# SmartCart-B1-Modules.net
KiCad netlist of a schematic drawn in EasyEDA
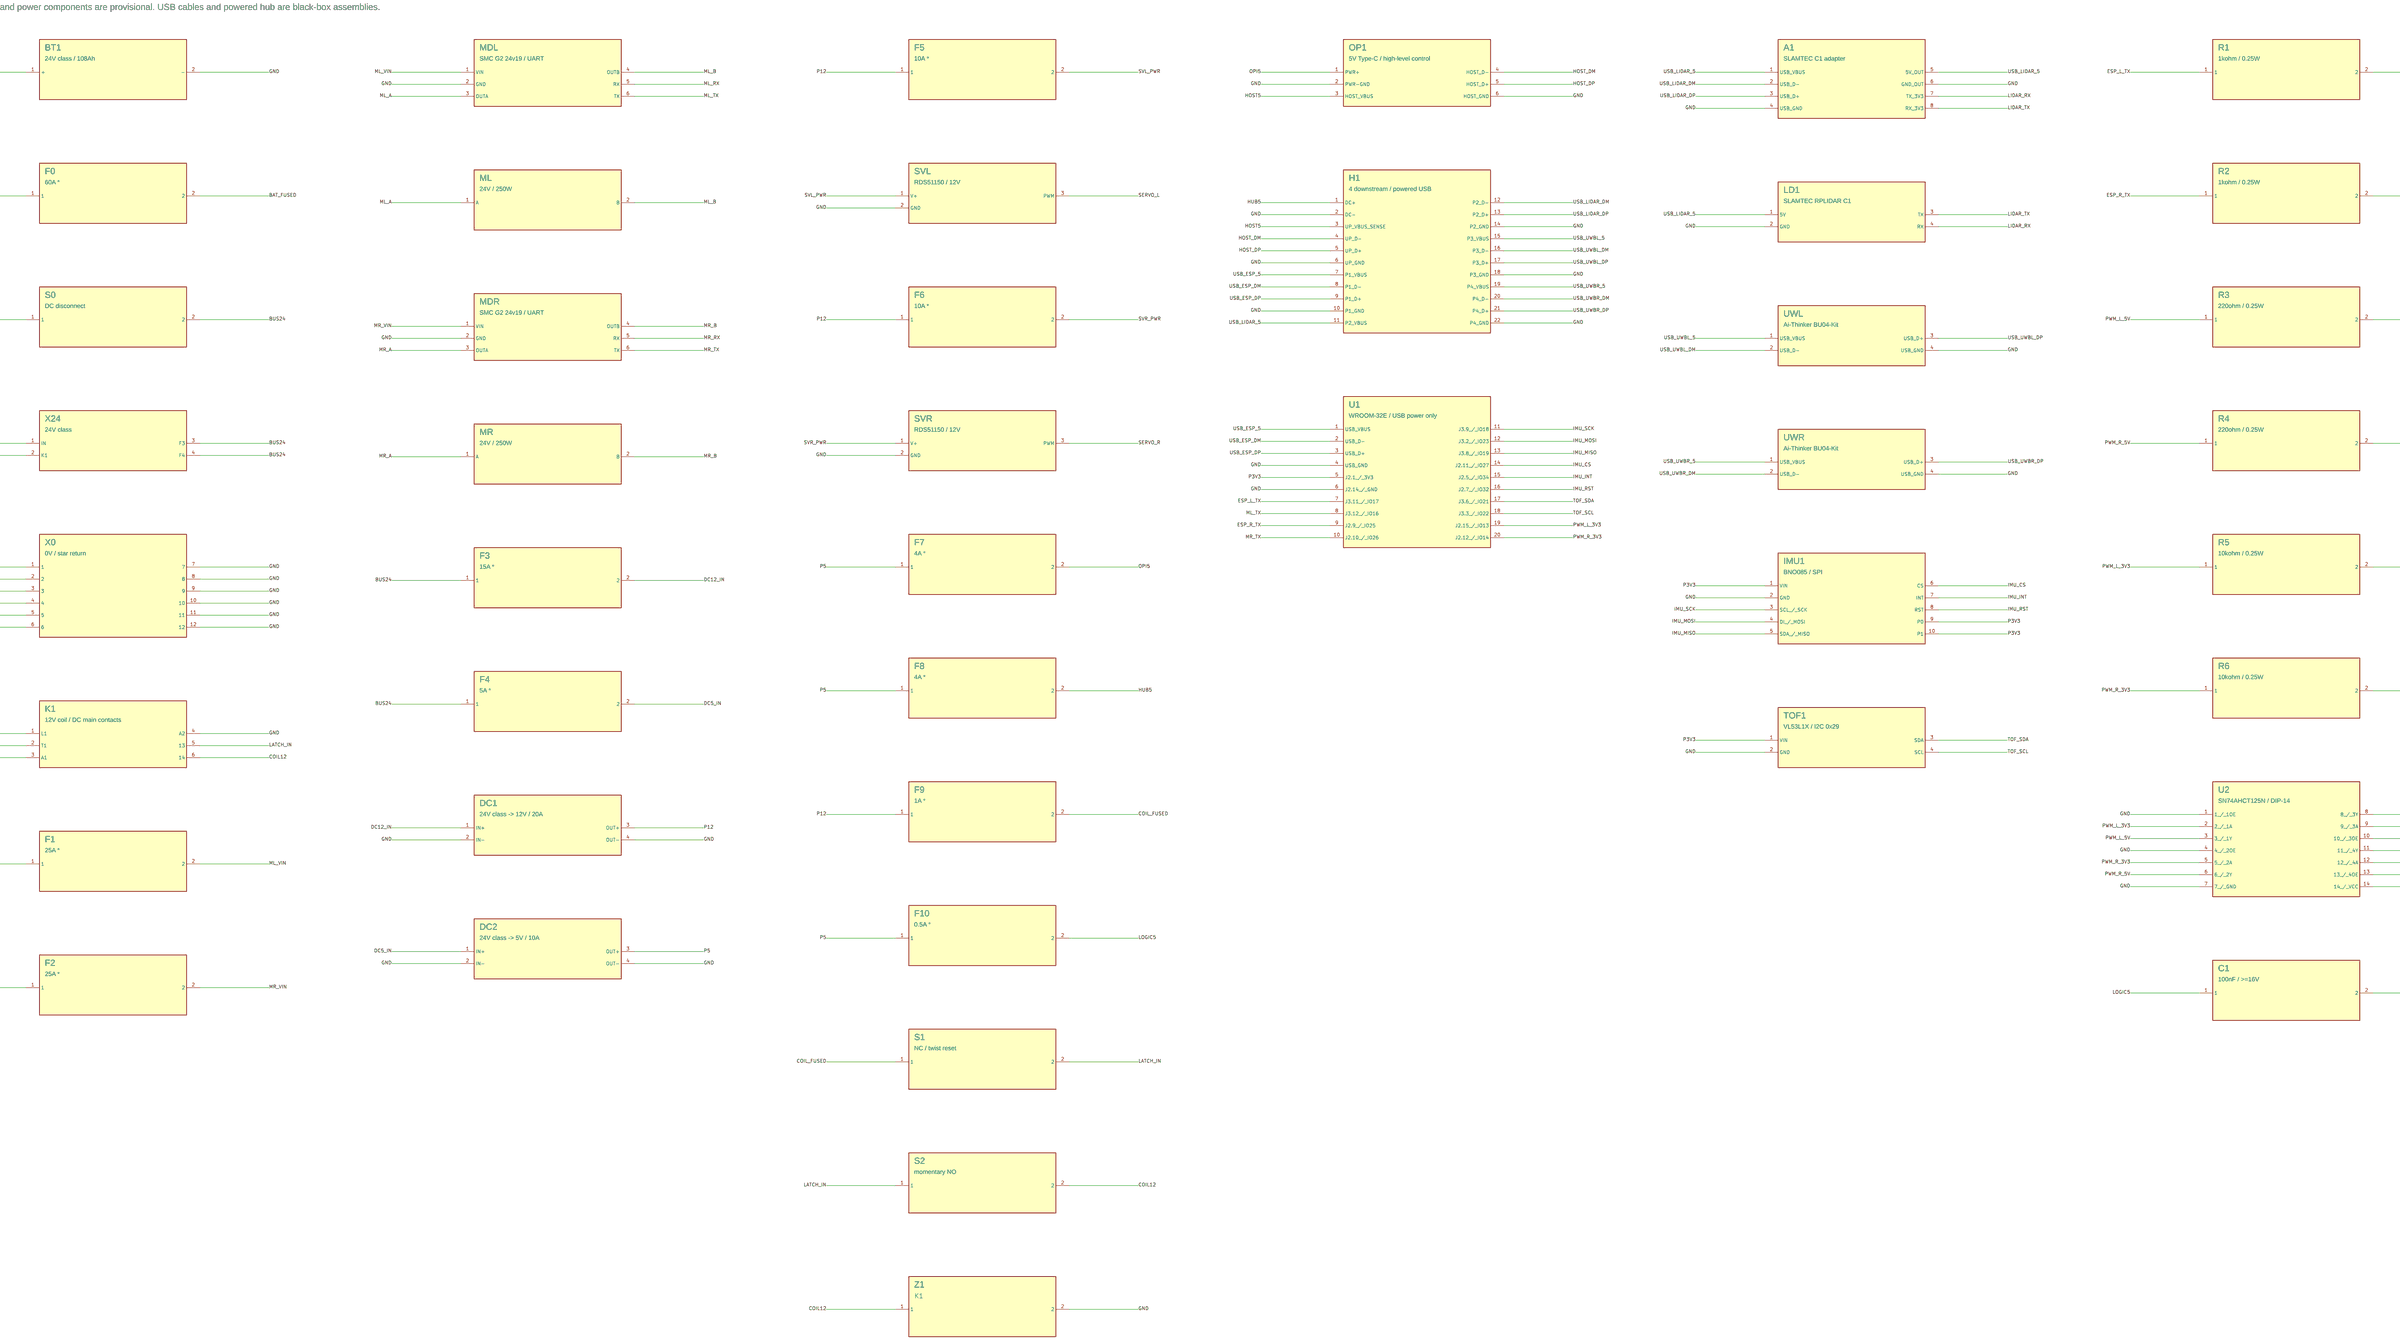
[diagram p0: schematic sheet]

(export (version "E")
  (design (tool "Eeschema 10.0.6"))
  (components
    (comp (ref "A1") (value "SLAMTEC C1 adapter") (libsource (lib "") (part "A1")))
    (comp (ref "BT1") (value "24V class / 108Ah") (libsource (lib "") (part "BT1")))
    (comp (ref "C1") (value "100nF / >=16V") (libsource (lib "") (part "C1")))
    (comp (ref "DC1") (value "24V class -> 12V / 20A") (libsource (lib "") (part "DC1")))
    (comp (ref "DC2") (value "24V class -> 5V / 10A") (libsource (lib "") (part "DC2")))
    (comp (ref "F0") (value "60A *") (libsource (lib "") (part "F0")))
    (comp (ref "F1") (value "25A *") (libsource (lib "") (part "F1")))
    (comp (ref "F2") (value "25A *") (libsource (lib "") (part "F2")))
    (comp (ref "F3") (value "15A *") (libsource (lib "") (part "F3")))
    (comp (ref "F4") (value "5A *") (libsource (lib "") (part "F4")))
    (comp (ref "F5") (value "10A *") (libsource (lib "") (part "F5")))
    (comp (ref "F6") (value "10A *") (libsource (lib "") (part "F6")))
    (comp (ref "F7") (value "4A *") (libsource (lib "") (part "F7")))
    (comp (ref "F8") (value "4A *") (libsource (lib "") (part "F8")))
    (comp (ref "F9") (value "1A *") (libsource (lib "") (part "F9")))
    (comp (ref "F10") (value "0.5A *") (libsource (lib "") (part "F10")))
    (comp (ref "H1") (value "4 downstream / powered USB") (libsource (lib "") (part "H1")))
    (comp (ref "IMU1") (value "BNO085 / SPI") (libsource (lib "") (part "IMU1")))
    (comp (ref "K1") (value "12V coil / DC main contacts") (libsource (lib "") (part "K1")))
    (comp (ref "LD1") (value "SLAMTEC RPLIDAR C1") (libsource (lib "") (part "LD1")))
    (comp (ref "MDL") (value "SMC G2 24v19 / UART") (libsource (lib "") (part "MDL")))
    (comp (ref "MDR") (value "SMC G2 24v19 / UART") (libsource (lib "") (part "MDR")))
    (comp (ref "ML") (value "24V / 250W") (libsource (lib "") (part "ML")))
    (comp (ref "MR") (value "24V / 250W") (libsource (lib "") (part "MR")))
    (comp (ref "OP1") (value "5V Type-C / high-level control") (libsource (lib "") (part "OP1")))
    (comp (ref "R1") (value "1kohm / 0.25W") (libsource (lib "") (part "R1")))
    (comp (ref "R2") (value "1kohm / 0.25W") (libsource (lib "") (part "R2")))
    (comp (ref "R3") (value "220ohm / 0.25W") (libsource (lib "") (part "R3")))
    (comp (ref "R4") (value "220ohm / 0.25W") (libsource (lib "") (part "R4")))
    (comp (ref "R5") (value "10kohm / 0.25W") (libsource (lib "") (part "R5")))
    (comp (ref "R6") (value "10kohm / 0.25W") (libsource (lib "") (part "R6")))
    (comp (ref "S0") (value "DC disconnect") (libsource (lib "") (part "S0")))
    (comp (ref "S1") (value "NC / twist reset") (libsource (lib "") (part "S1")))
    (comp (ref "S2") (value "momentary NO") (libsource (lib "") (part "S2")))
    (comp (ref "SVL") (value "RDS51150 / 12V") (libsource (lib "") (part "SVL")))
    (comp (ref "SVR") (value "RDS51150 / 12V") (libsource (lib "") (part "SVR")))
    (comp (ref "TOF1") (value "VL53L1X / I2C 0x29") (libsource (lib "") (part "TOF1")))
    (comp (ref "U1") (value "WROOM-32E / USB power only") (libsource (lib "") (part "U1")))
    (comp (ref "U2") (value "SN74AHCT125N / DIP-14") (libsource (lib "") (part "U2")))
    (comp (ref "UWL") (value "Ai-Thinker BU04-Kit") (libsource (lib "") (part "UWL")))
    (comp (ref "UWR") (value "Ai-Thinker BU04-Kit") (libsource (lib "") (part "UWR")))
    (comp (ref "X0") (value "0V / star return") (libsource (lib "") (part "X0")))
    (comp (ref "X24") (value "24V class") (libsource (lib "") (part "X24")))
    (comp (ref "Z1") (value "K1 지정품") (libsource (lib "") (part "Z1")))
  )
  (nets
    (net (code "1") (name "/BAT_FUSED") (class "Default")
      (node (ref "F0") (pin "2") (pinfunction "2_2") (pintype "unspecified"))
      (node (ref "S0") (pin "1") (pinfunction "1_1") (pintype "unspecified"))
    )
    (net (code "2") (name "/BAT_POS") (class "Default")
      (node (ref "BT1") (pin "1") (pinfunction "+_1") (pintype "unspecified"))
      (node (ref "F0") (pin "1") (pinfunction "1_1") (pintype "unspecified"))
    )
    (net (code "3") (name "/BUS24") (class "Default")
      (node (ref "F3") (pin "1") (pinfunction "1_1") (pintype "unspecified"))
      (node (ref "F4") (pin "1") (pinfunction "1_1") (pintype "unspecified"))
      (node (ref "K1") (pin "1") (pinfunction "L1_1") (pintype "unspecified"))
      (node (ref "S0") (pin "2") (pinfunction "2_2") (pintype "unspecified"))
      (node (ref "X24") (pin "1") (pinfunction "IN_1") (pintype "unspecified"))
      (node (ref "X24") (pin "2") (pinfunction "K1_2") (pintype "unspecified"))
      (node (ref "X24") (pin "3") (pinfunction "F3_3") (pintype "unspecified"))
      (node (ref "X24") (pin "4") (pinfunction "F4_4") (pintype "unspecified"))
    )
    (net (code "4") (name "/COIL12") (class "Default")
      (node (ref "K1") (pin "3") (pinfunction "A1_3") (pintype "unspecified"))
      (node (ref "K1") (pin "6") (pinfunction "14_6") (pintype "unspecified"))
      (node (ref "S2") (pin "2") (pinfunction "2_2") (pintype "unspecified"))
      (node (ref "Z1") (pin "1") (pinfunction "1_1") (pintype "unspecified"))
    )
    (net (code "5") (name "/COIL_FUSED") (class "Default")
      (node (ref "F9") (pin "2") (pinfunction "2_2") (pintype "unspecified"))
      (node (ref "S1") (pin "1") (pinfunction "1_1") (pintype "unspecified"))
    )
    (net (code "6") (name "/DC5_IN") (class "Default")
      (node (ref "DC2") (pin "1") (pinfunction "IN+_1") (pintype "unspecified"))
      (node (ref "F4") (pin "2") (pinfunction "2_2") (pintype "unspecified"))
    )
    (net (code "7") (name "/DC12_IN") (class "Default")
      (node (ref "DC1") (pin "1") (pinfunction "IN+_1") (pintype "unspecified"))
      (node (ref "F3") (pin "2") (pinfunction "2_2") (pintype "unspecified"))
    )
    (net (code "8") (name "/DRIVE24") (class "Default")
      (node (ref "F1") (pin "1") (pinfunction "1_1") (pintype "unspecified"))
      (node (ref "F2") (pin "1") (pinfunction "1_1") (pintype "unspecified"))
      (node (ref "K1") (pin "2") (pinfunction "T1_2") (pintype "unspecified"))
    )
    (net (code "9") (name "/ESP_L_TX") (class "Default")
      (node (ref "R1") (pin "1") (pinfunction "1_1") (pintype "unspecified"))
      (node (ref "U1") (pin "7") (pinfunction "J3.11_/_IO17_7") (pintype "unspecified"))
    )
    (net (code "10") (name "/ESP_R_TX") (class "Default")
      (node (ref "R2") (pin "1") (pinfunction "1_1") (pintype "unspecified"))
      (node (ref "U1") (pin "9") (pinfunction "J2.9_/_IO25_9") (pintype "unspecified"))
    )
    (net (code "11") (name "/GND") (class "Default")
      (node (ref "A1") (pin "4") (pinfunction "USB_GND_4") (pintype "unspecified"))
      (node (ref "A1") (pin "6") (pinfunction "GND_OUT_6") (pintype "unspecified"))
      (node (ref "BT1") (pin "2") (pinfunction "-_2") (pintype "unspecified"))
      (node (ref "C1") (pin "2") (pinfunction "2_2") (pintype "unspecified"))
      (node (ref "DC1") (pin "2") (pinfunction "IN-_2") (pintype "unspecified"))
      (node (ref "DC1") (pin "4") (pinfunction "OUT-_4") (pintype "unspecified"))
      (node (ref "DC2") (pin "2") (pinfunction "IN-_2") (pintype "unspecified"))
      (node (ref "DC2") (pin "4") (pinfunction "OUT-_4") (pintype "unspecified"))
      (node (ref "H1") (pin "10") (pinfunction "P1_GND_10") (pintype "unspecified"))
      (node (ref "H1") (pin "14") (pinfunction "P2_GND_14") (pintype "unspecified"))
      (node (ref "H1") (pin "18") (pinfunction "P3_GND_18") (pintype "unspecified"))
      (node (ref "H1") (pin "2") (pinfunction "DC-_2") (pintype "unspecified"))
      (node (ref "H1") (pin "22") (pinfunction "P4_GND_22") (pintype "unspecified"))
      (node (ref "H1") (pin "6") (pinfunction "UP_GND_6") (pintype "unspecified"))
      (node (ref "IMU1") (pin "2") (pinfunction "GND_2") (pintype "unspecified"))
      (node (ref "K1") (pin "4") (pinfunction "A2_4") (pintype "unspecified"))
      (node (ref "LD1") (pin "2") (pinfunction "GND_2") (pintype "unspecified"))
      (node (ref "MDL") (pin "2") (pinfunction "GND_2") (pintype "unspecified"))
      (node (ref "MDR") (pin "2") (pinfunction "GND_2") (pintype "unspecified"))
      (node (ref "OP1") (pin "2") (pinfunction "PWR-GND_2") (pintype "unspecified"))
      (node (ref "OP1") (pin "6") (pinfunction "HOST_GND_6") (pintype "unspecified"))
      (node (ref "R5") (pin "2") (pinfunction "2_2") (pintype "unspecified"))
      (node (ref "R6") (pin "2") (pinfunction "2_2") (pintype "unspecified"))
      (node (ref "SVL") (pin "2") (pinfunction "GND_2") (pintype "unspecified"))
      (node (ref "SVR") (pin "2") (pinfunction "GND_2") (pintype "unspecified"))
      (node (ref "TOF1") (pin "2") (pinfunction "GND_2") (pintype "unspecified"))
      (node (ref "U1") (pin "4") (pinfunction "USB_GND_4") (pintype "unspecified"))
      (node (ref "U1") (pin "6") (pinfunction "J2.14_/_GND_6") (pintype "unspecified"))
      (node (ref "U2") (pin "1") (pinfunction "1_/_1OE_1") (pintype "unspecified"))
      (node (ref "U2") (pin "12") (pinfunction "12_/_4A_12") (pintype "unspecified"))
      (node (ref "U2") (pin "4") (pinfunction "4_/_2OE_4") (pintype "unspecified"))
      (node (ref "U2") (pin "7") (pinfunction "7_/_GND_7") (pintype "unspecified"))
      (node (ref "U2") (pin "9") (pinfunction "9_/_3A_9") (pintype "unspecified"))
      (node (ref "UWL") (pin "4") (pinfunction "USB_GND_4") (pintype "unspecified"))
      (node (ref "UWR") (pin "4") (pinfunction "USB_GND_4") (pintype "unspecified"))
      (node (ref "X0") (pin "1") (pinfunction "1_1") (pintype "unspecified"))
      (node (ref "X0") (pin "10") (pinfunction "10_10") (pintype "unspecified"))
      (node (ref "X0") (pin "11") (pinfunction "11_11") (pintype "unspecified"))
      (node (ref "X0") (pin "12") (pinfunction "12_12") (pintype "unspecified"))
      (node (ref "X0") (pin "2") (pinfunction "2_2") (pintype "unspecified"))
      (node (ref "X0") (pin "3") (pinfunction "3_3") (pintype "unspecified"))
      (node (ref "X0") (pin "4") (pinfunction "4_4") (pintype "unspecified"))
      (node (ref "X0") (pin "5") (pinfunction "5_5") (pintype "unspecified"))
      (node (ref "X0") (pin "6") (pinfunction "6_6") (pintype "unspecified"))
      (node (ref "X0") (pin "7") (pinfunction "7_7") (pintype "unspecified"))
      (node (ref "X0") (pin "8") (pinfunction "8_8") (pintype "unspecified"))
      (node (ref "X0") (pin "9") (pinfunction "9_9") (pintype "unspecified"))
      (node (ref "Z1") (pin "2") (pinfunction "2_2") (pintype "unspecified"))
    )
    (net (code "12") (name "/HOST5") (class "Default")
      (node (ref "H1") (pin "3") (pinfunction "UP_VBUS_SENSE_3") (pintype "unspecified"))
      (node (ref "OP1") (pin "3") (pinfunction "HOST_VBUS_3") (pintype "unspecified"))
    )
    (net (code "13") (name "/HOST_DM") (class "Default")
      (node (ref "H1") (pin "4") (pinfunction "UP_D-_4") (pintype "unspecified"))
      (node (ref "OP1") (pin "4") (pinfunction "HOST_D-_4") (pintype "unspecified"))
    )
    (net (code "14") (name "/HOST_DP") (class "Default")
      (node (ref "H1") (pin "5") (pinfunction "UP_D+_5") (pintype "unspecified"))
      (node (ref "OP1") (pin "5") (pinfunction "HOST_D+_5") (pintype "unspecified"))
    )
    (net (code "15") (name "/HUB5") (class "Default")
      (node (ref "F8") (pin "2") (pinfunction "2_2") (pintype "unspecified"))
      (node (ref "H1") (pin "1") (pinfunction "DC+_1") (pintype "unspecified"))
    )
    (net (code "16") (name "/IMU_CS") (class "Default")
      (node (ref "IMU1") (pin "6") (pinfunction "CS_6") (pintype "unspecified"))
      (node (ref "U1") (pin "14") (pinfunction "J2.11_/_IO27_14") (pintype "unspecified"))
    )
    (net (code "17") (name "/IMU_INT") (class "Default")
      (node (ref "IMU1") (pin "7") (pinfunction "INT_7") (pintype "unspecified"))
      (node (ref "U1") (pin "15") (pinfunction "J2.5_/_IO34_15") (pintype "unspecified"))
    )
    (net (code "18") (name "/IMU_MISO") (class "Default")
      (node (ref "IMU1") (pin "5") (pinfunction "SDA_/_MISO_5") (pintype "unspecified"))
      (node (ref "U1") (pin "13") (pinfunction "J3.8_/_IO19_13") (pintype "unspecified"))
    )
    (net (code "19") (name "/IMU_MOSI") (class "Default")
      (node (ref "IMU1") (pin "4") (pinfunction "DI_/_MOSI_4") (pintype "unspecified"))
      (node (ref "U1") (pin "12") (pinfunction "J3.2_/_IO23_12") (pintype "unspecified"))
    )
    (net (code "20") (name "/IMU_RST") (class "Default")
      (node (ref "IMU1") (pin "8") (pinfunction "RST_8") (pintype "unspecified"))
      (node (ref "U1") (pin "16") (pinfunction "J2.7_/_IO32_16") (pintype "unspecified"))
    )
    (net (code "21") (name "/IMU_SCK") (class "Default")
      (node (ref "IMU1") (pin "3") (pinfunction "SCL_/_SCK_3") (pintype "unspecified"))
      (node (ref "U1") (pin "11") (pinfunction "J3.9_/_IO18_11") (pintype "unspecified"))
    )
    (net (code "22") (name "/LATCH_IN") (class "Default")
      (node (ref "K1") (pin "5") (pinfunction "13_5") (pintype "unspecified"))
      (node (ref "S1") (pin "2") (pinfunction "2_2") (pintype "unspecified"))
      (node (ref "S2") (pin "1") (pinfunction "1_1") (pintype "unspecified"))
    )
    (net (code "23") (name "/LIDAR_RX") (class "Default")
      (node (ref "A1") (pin "7") (pinfunction "TX_3V3_7") (pintype "unspecified"))
      (node (ref "LD1") (pin "4") (pinfunction "RX_4") (pintype "unspecified"))
    )
    (net (code "24") (name "/LIDAR_TX") (class "Default")
      (node (ref "A1") (pin "8") (pinfunction "RX_3V3_8") (pintype "unspecified"))
      (node (ref "LD1") (pin "3") (pinfunction "TX_3") (pintype "unspecified"))
    )
    (net (code "25") (name "/LOGIC5") (class "Default")
      (node (ref "C1") (pin "1") (pinfunction "1_1") (pintype "unspecified"))
      (node (ref "F10") (pin "2") (pinfunction "2_2") (pintype "unspecified"))
      (node (ref "U2") (pin "10") (pinfunction "10_/_3OE_10") (pintype "unspecified"))
      (node (ref "U2") (pin "13") (pinfunction "13_/_4OE_13") (pintype "unspecified"))
      (node (ref "U2") (pin "14") (pinfunction "14_/_VCC_14") (pintype "unspecified"))
    )
    (net (code "26") (name "/ML_A") (class "Default")
      (node (ref "MDL") (pin "3") (pinfunction "OUTA_3") (pintype "unspecified"))
      (node (ref "ML") (pin "1") (pinfunction "A_1") (pintype "unspecified"))
    )
    (net (code "27") (name "/ML_B") (class "Default")
      (node (ref "MDL") (pin "4") (pinfunction "OUTB_4") (pintype "unspecified"))
      (node (ref "ML") (pin "2") (pinfunction "B_2") (pintype "unspecified"))
    )
    (net (code "28") (name "/ML_RX") (class "Default")
      (node (ref "MDL") (pin "5") (pinfunction "RX_5") (pintype "unspecified"))
      (node (ref "R1") (pin "2") (pinfunction "2_2") (pintype "unspecified"))
    )
    (net (code "29") (name "/ML_TX") (class "Default")
      (node (ref "MDL") (pin "6") (pinfunction "TX_6") (pintype "unspecified"))
      (node (ref "U1") (pin "8") (pinfunction "J3.12_/_IO16_8") (pintype "unspecified"))
    )
    (net (code "30") (name "/ML_VIN") (class "Default")
      (node (ref "F1") (pin "2") (pinfunction "2_2") (pintype "unspecified"))
      (node (ref "MDL") (pin "1") (pinfunction "VIN_1") (pintype "unspecified"))
    )
    (net (code "31") (name "/MR_A") (class "Default")
      (node (ref "MDR") (pin "3") (pinfunction "OUTA_3") (pintype "unspecified"))
      (node (ref "MR") (pin "1") (pinfunction "A_1") (pintype "unspecified"))
    )
    (net (code "32") (name "/MR_B") (class "Default")
      (node (ref "MDR") (pin "4") (pinfunction "OUTB_4") (pintype "unspecified"))
      (node (ref "MR") (pin "2") (pinfunction "B_2") (pintype "unspecified"))
    )
    (net (code "33") (name "/MR_RX") (class "Default")
      (node (ref "MDR") (pin "5") (pinfunction "RX_5") (pintype "unspecified"))
      (node (ref "R2") (pin "2") (pinfunction "2_2") (pintype "unspecified"))
    )
    (net (code "34") (name "/MR_TX") (class "Default")
      (node (ref "MDR") (pin "6") (pinfunction "TX_6") (pintype "unspecified"))
      (node (ref "U1") (pin "10") (pinfunction "J2.10_/_IO26_10") (pintype "unspecified"))
    )
    (net (code "35") (name "/MR_VIN") (class "Default")
      (node (ref "F2") (pin "2") (pinfunction "2_2") (pintype "unspecified"))
      (node (ref "MDR") (pin "1") (pinfunction "VIN_1") (pintype "unspecified"))
    )
    (net (code "36") (name "/NC_U2_8") (class "Default")
      (node (ref "U2") (pin "8") (pinfunction "8_/_3Y_8") (pintype "unspecified"))
    )
    (net (code "37") (name "/NC_U2_11") (class "Default")
      (node (ref "U2") (pin "11") (pinfunction "11_/_4Y_11") (pintype "unspecified"))
    )
    (net (code "38") (name "/OPI5") (class "Default")
      (node (ref "F7") (pin "2") (pinfunction "2_2") (pintype "unspecified"))
      (node (ref "OP1") (pin "1") (pinfunction "PWR+_1") (pintype "unspecified"))
    )
    (net (code "39") (name "/P3V3") (class "Default")
      (node (ref "IMU1") (pin "1") (pinfunction "VIN_1") (pintype "unspecified"))
      (node (ref "IMU1") (pin "10") (pinfunction "P1_10") (pintype "unspecified"))
      (node (ref "IMU1") (pin "9") (pinfunction "P0_9") (pintype "unspecified"))
      (node (ref "TOF1") (pin "1") (pinfunction "VIN_1") (pintype "unspecified"))
      (node (ref "U1") (pin "5") (pinfunction "J2.1_/_3V3_5") (pintype "unspecified"))
    )
    (net (code "40") (name "/P5") (class "Default")
      (node (ref "DC2") (pin "3") (pinfunction "OUT+_3") (pintype "unspecified"))
      (node (ref "F10") (pin "1") (pinfunction "1_1") (pintype "unspecified"))
      (node (ref "F7") (pin "1") (pinfunction "1_1") (pintype "unspecified"))
      (node (ref "F8") (pin "1") (pinfunction "1_1") (pintype "unspecified"))
    )
    (net (code "41") (name "/P12") (class "Default")
      (node (ref "DC1") (pin "3") (pinfunction "OUT+_3") (pintype "unspecified"))
      (node (ref "F5") (pin "1") (pinfunction "1_1") (pintype "unspecified"))
      (node (ref "F6") (pin "1") (pinfunction "1_1") (pintype "unspecified"))
      (node (ref "F9") (pin "1") (pinfunction "1_1") (pintype "unspecified"))
    )
    (net (code "42") (name "/PWM_L_3V3") (class "Default")
      (node (ref "R5") (pin "1") (pinfunction "1_1") (pintype "unspecified"))
      (node (ref "U1") (pin "19") (pinfunction "J2.15_/_IO13_19") (pintype "unspecified"))
      (node (ref "U2") (pin "2") (pinfunction "2_/_1A_2") (pintype "unspecified"))
    )
    (net (code "43") (name "/PWM_L_5V") (class "Default")
      (node (ref "R3") (pin "1") (pinfunction "1_1") (pintype "unspecified"))
      (node (ref "U2") (pin "3") (pinfunction "3_/_1Y_3") (pintype "unspecified"))
    )
    (net (code "44") (name "/PWM_R_3V3") (class "Default")
      (node (ref "R6") (pin "1") (pinfunction "1_1") (pintype "unspecified"))
      (node (ref "U1") (pin "20") (pinfunction "J2.12_/_IO14_20") (pintype "unspecified"))
      (node (ref "U2") (pin "5") (pinfunction "5_/_2A_5") (pintype "unspecified"))
    )
    (net (code "45") (name "/PWM_R_5V") (class "Default")
      (node (ref "R4") (pin "1") (pinfunction "1_1") (pintype "unspecified"))
      (node (ref "U2") (pin "6") (pinfunction "6_/_2Y_6") (pintype "unspecified"))
    )
    (net (code "46") (name "/SERVO_L") (class "Default")
      (node (ref "R3") (pin "2") (pinfunction "2_2") (pintype "unspecified"))
      (node (ref "SVL") (pin "3") (pinfunction "PWM_3") (pintype "unspecified"))
    )
    (net (code "47") (name "/SERVO_R") (class "Default")
      (node (ref "R4") (pin "2") (pinfunction "2_2") (pintype "unspecified"))
      (node (ref "SVR") (pin "3") (pinfunction "PWM_3") (pintype "unspecified"))
    )
    (net (code "48") (name "/SVL_PWR") (class "Default")
      (node (ref "F5") (pin "2") (pinfunction "2_2") (pintype "unspecified"))
      (node (ref "SVL") (pin "1") (pinfunction "V+_1") (pintype "unspecified"))
    )
    (net (code "49") (name "/SVR_PWR") (class "Default")
      (node (ref "F6") (pin "2") (pinfunction "2_2") (pintype "unspecified"))
      (node (ref "SVR") (pin "1") (pinfunction "V+_1") (pintype "unspecified"))
    )
    (net (code "50") (name "/TOF_SCL") (class "Default")
      (node (ref "TOF1") (pin "4") (pinfunction "SCL_4") (pintype "unspecified"))
      (node (ref "U1") (pin "18") (pinfunction "J3.3_/_IO22_18") (pintype "unspecified"))
    )
    (net (code "51") (name "/TOF_SDA") (class "Default")
      (node (ref "TOF1") (pin "3") (pinfunction "SDA_3") (pintype "unspecified"))
      (node (ref "U1") (pin "17") (pinfunction "J3.6_/_IO21_17") (pintype "unspecified"))
    )
    (net (code "52") (name "/USB_ESP_5") (class "Default")
      (node (ref "H1") (pin "7") (pinfunction "P1_VBUS_7") (pintype "unspecified"))
      (node (ref "U1") (pin "1") (pinfunction "USB_VBUS_1") (pintype "unspecified"))
    )
    (net (code "53") (name "/USB_ESP_DM") (class "Default")
      (node (ref "H1") (pin "8") (pinfunction "P1_D-_8") (pintype "unspecified"))
      (node (ref "U1") (pin "2") (pinfunction "USB_D-_2") (pintype "unspecified"))
    )
    (net (code "54") (name "/USB_ESP_DP") (class "Default")
      (node (ref "H1") (pin "9") (pinfunction "P1_D+_9") (pintype "unspecified"))
      (node (ref "U1") (pin "3") (pinfunction "USB_D+_3") (pintype "unspecified"))
    )
    (net (code "55") (name "/USB_LIDAR_5") (class "Default")
      (node (ref "A1") (pin "1") (pinfunction "USB_VBUS_1") (pintype "unspecified"))
      (node (ref "A1") (pin "5") (pinfunction "5V_OUT_5") (pintype "unspecified"))
      (node (ref "H1") (pin "11") (pinfunction "P2_VBUS_11") (pintype "unspecified"))
      (node (ref "LD1") (pin "1") (pinfunction "5V_1") (pintype "unspecified"))
    )
    (net (code "56") (name "/USB_LIDAR_DM") (class "Default")
      (node (ref "A1") (pin "2") (pinfunction "USB_D-_2") (pintype "unspecified"))
      (node (ref "H1") (pin "12") (pinfunction "P2_D-_12") (pintype "unspecified"))
    )
    (net (code "57") (name "/USB_LIDAR_DP") (class "Default")
      (node (ref "A1") (pin "3") (pinfunction "USB_D+_3") (pintype "unspecified"))
      (node (ref "H1") (pin "13") (pinfunction "P2_D+_13") (pintype "unspecified"))
    )
    (net (code "58") (name "/USB_UWBL_5") (class "Default")
      (node (ref "H1") (pin "15") (pinfunction "P3_VBUS_15") (pintype "unspecified"))
      (node (ref "UWL") (pin "1") (pinfunction "USB_VBUS_1") (pintype "unspecified"))
    )
    (net (code "59") (name "/USB_UWBL_DM") (class "Default")
      (node (ref "H1") (pin "16") (pinfunction "P3_D-_16") (pintype "unspecified"))
      (node (ref "UWL") (pin "2") (pinfunction "USB_D-_2") (pintype "unspecified"))
    )
    (net (code "60") (name "/USB_UWBL_DP") (class "Default")
      (node (ref "H1") (pin "17") (pinfunction "P3_D+_17") (pintype "unspecified"))
      (node (ref "UWL") (pin "3") (pinfunction "USB_D+_3") (pintype "unspecified"))
    )
    (net (code "61") (name "/USB_UWBR_5") (class "Default")
      (node (ref "H1") (pin "19") (pinfunction "P4_VBUS_19") (pintype "unspecified"))
      (node (ref "UWR") (pin "1") (pinfunction "USB_VBUS_1") (pintype "unspecified"))
    )
    (net (code "62") (name "/USB_UWBR_DM") (class "Default")
      (node (ref "H1") (pin "20") (pinfunction "P4_D-_20") (pintype "unspecified"))
      (node (ref "UWR") (pin "2") (pinfunction "USB_D-_2") (pintype "unspecified"))
    )
    (net (code "63") (name "/USB_UWBR_DP") (class "Default")
      (node (ref "H1") (pin "21") (pinfunction "P4_D+_21") (pintype "unspecified"))
      (node (ref "UWR") (pin "3") (pinfunction "USB_D+_3") (pintype "unspecified"))
    )
  )
)
